# PowerSupply.net
KiCad netlist of a schematic drawn in Altium Designer
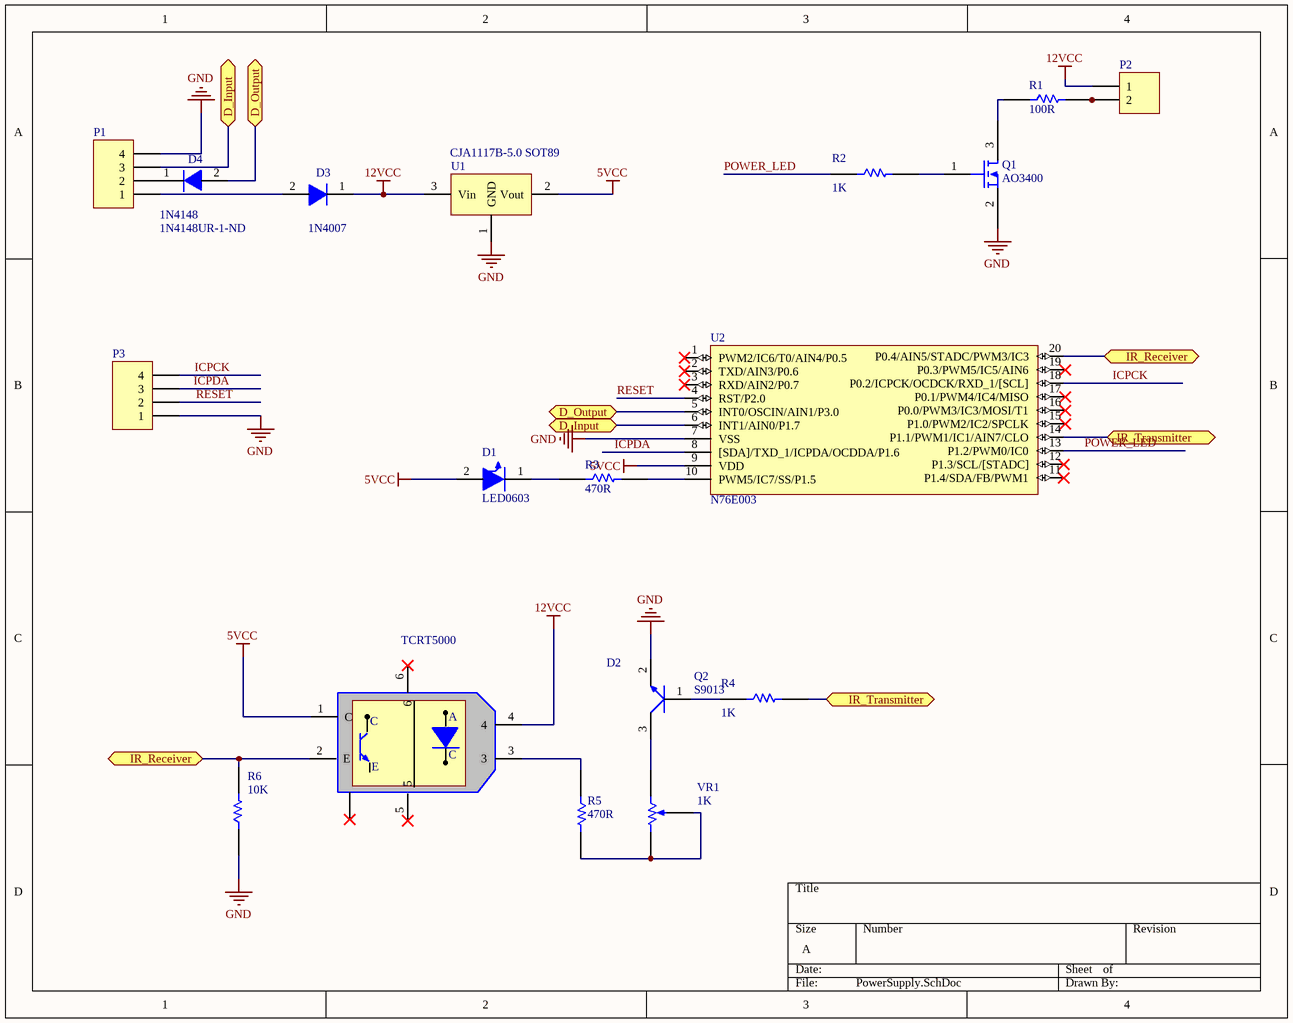
[diagram p0: PowerSupply.SchDoc]

(export (version "E")
  (design (tool "Eeschema 10.0.6"))
  (components
    (comp (ref "D1")
      (value "LED0603")
      (footprint "DIOC1608X06N")
      (libsource (lib "Integrated_Library1") (part "LED0603"))
    )
    (comp (ref "D2")
      (value "TCRT5000")
      (footprint "TCRT5000")
      (libsource (lib "Integrated_Library1") (part "TCRT5000"))
    )
    (comp (ref "D3")
      (value "1N4007")
      (footprint "SODFL504X244-2N")
      (description "1N4007_SMD")
      (libsource (lib "Integrated_Library1") (part "1N4007_SMD Diode"))
    )
    (comp (ref "D4")
      (value "1N4148")
      (footprint "DIOMELF3515N")
      (description "DIODE GEN PURP 75V 200MA DO213AA")
      (fields (field (name "SUPPLIER PART NUMBER 1") "1N4148UR-1-ND"))
      (libsource (lib "Integrated_Library1") (part "1N4148_SMD"))
    )
    (comp (ref "P1")
      (value "~")
      (footprint "HDR1X4H")
      (description "Header, 4-Pin, Right Angle")
      (fields (field (name "PUBLISHER") "Altium Limited"))
      (libsource (lib "Miscellaneous Connectors") (part "Header 4H"))
    )
    (comp (ref "P2")
      (value "~")
      (footprint "HDR1X2")
      (description "Header, 2-Pin")
      (fields (field (name "PUBLISHER") "Altium Limited"))
      (libsource (lib "Miscellaneous Connectors") (part "Header 2"))
    )
    (comp (ref "P3")
      (value "~")
      (footprint "HDR1X4")
      (description "Header, 4-Pin")
      (fields (field (name "PUBLISHER") "Altium Limited"))
      (libsource (lib "Miscellaneous Connectors") (part "Header 4"))
    )
    (comp (ref "Q1")
      (value "AO3400")
      (footprint "SOT95P278X125-3N")
      (description "AO3400  MOSFET SOT23-3")
      (libsource (lib "Integrated_Library1") (part "AO3400  MOSFET SOT23-3"))
    )
    (comp (ref "Q2")
      (value "S9013")
      (footprint "SOT95P278X125-3N")
      (description "SOT-23 Plastic-Encapsulate Transistors")
      (libsource (lib "Integrated_Library1") (part "Transitor S9013 NPN"))
    )
    (comp (ref "R1")
      (value "100R")
      (footprint "RESC2608X06N_0603")
      (description "Thick Film Resistors - SMD 0603 100OHMS 5% 1/10WATT")
      (libsource (lib "Integrated_Library1") (part "R100_0603_5%"))
    )
    (comp (ref "R2")
      (value "1K")
      (footprint "RESC2608X06N_0603")
      (description "Thick Film Resistors - SMD 0603 1kOHMS 5% 1/10WATT")
      (libsource (lib "Integrated_Library1") (part "1k_0603_5%"))
    )
    (comp (ref "R3")
      (value "470R")
      (footprint "RESC2608X06N_0603")
      (description "Thick Film Resistors - SMD 470 ohm 5%")
      (libsource (lib "Integrated_Library1") (part "R470_0603_5%"))
    )
    (comp (ref "R4")
      (value "1K")
      (footprint "RESC2608X06N_0603")
      (description "Thick Film Resistors - SMD 0603 1kOHMS 5% 1/10WATT")
      (libsource (lib "Integrated_Library1") (part "1k_0603_5%"))
    )
    (comp (ref "R5")
      (value "470R")
      (footprint "RESC2608X06N_0603")
      (description "Thick Film Resistors - SMD 470 ohm 5%")
      (libsource (lib "Integrated_Library1") (part "R470_0603_5%"))
    )
    (comp (ref "R6")
      (value "10K")
      (footprint "RESC2608X06N_0603")
      (description "RES SMD 10K OHM 1% 1/4W 0603")
      (libsource (lib "Integrated_Library1") (part "R10k_0603_5%"))
    )
    (comp (ref "U1")
      (value "CJA1117B-5.0 SOT89")
      (footprint "SOT89-150P409X160-3N")
      (description "CJA1117B-5.0 SOT89 Power IC 1A 5V_IC")
      (libsource (lib "Integrated_Library1") (part "CJA1117B-5.0 SOT89"))
    )
    (comp (ref "U2")
      (value "N76E003")
      (footprint "TSOP65P640X120-20N")
      (description "IC MCU 8BIT 18KB FLASH 20TSSOP")
      (libsource (lib "Integrated_Library1") (part "N76E003"))
    )
    (comp (ref "VR1")
      (value "1K")
      (footprint "Var_SMD_3x3")
      (description "Varistor 3x3 SMD 1KOhm 5% 1/10WATT")
      (libsource (lib "Integrated_Library1") (part "Varistor 3x3 SMD 1KOhm"))
    )
  )
  (nets
    (net (code "1") (name "/D_Input") (class "Default")
      (node (ref "P1") (pin "3") (pinfunction "3_3") (pintype "passive"))
      (node (ref "U2") (pin "6") (pinfunction "INT1/AIN0/P1.7_6") (pintype "bidirectional"))
    )
    (net (code "2") (name "/D_Output") (class "Default")
      (node (ref "D4") (pin "2") (pinfunction "A_2") (pintype "passive"))
      (node (ref "U2") (pin "5") (pinfunction "INT0/OSCIN/AIN1/P3.0_5") (pintype "bidirectional"))
    )
    (net (code "3") (name "/ICPCK") (class "Default")
      (node (ref "P3") (pin "4") (pinfunction "4_4") (pintype "passive"))
      (node (ref "U2") (pin "18") (pinfunction "P0.2/ICPCK/OCDCK/RXD_1/[SCL]_18") (pintype "bidirectional"))
    )
    (net (code "4") (name "/ICPDA") (class "Default")
      (node (ref "P3") (pin "3") (pinfunction "3_3") (pintype "passive"))
      (node (ref "U2") (pin "8") (pinfunction "[SDA]/TXD_1/ICPDA/OCDDA/P1.6_8") (pintype "power_in"))
    )
    (net (code "5") (name "/IR_Receiver") (class "Default")
      (node (ref "D2") (pin "2") (pinfunction "E_2") (pintype "passive"))
      (node (ref "R6") (pin "2") (pinfunction "2_2") (pintype "passive"))
      (node (ref "U2") (pin "20") (pinfunction "P0.4/AIN5/STADC/PWM3/IC3_20") (pintype "bidirectional"))
    )
    (net (code "6") (name "/IR_Transmitter") (class "Default")
      (node (ref "R4") (pin "2") (pinfunction "2_2") (pintype "passive"))
      (node (ref "U2") (pin "14") (pinfunction "P1.1/PWM1/IC1/AIN7/CLO_14") (pintype "bidirectional"))
    )
    (net (code "7") (name "/POWER_LED") (class "Default")
      (node (ref "R2") (pin "1") (pinfunction "1_1") (pintype "passive"))
      (node (ref "U2") (pin "13") (pinfunction "P1.2/PWM0/IC0_13") (pintype "bidirectional"))
    )
    (net (code "8") (name "/RESET") (class "Default")
      (node (ref "P3") (pin "2") (pinfunction "2_2") (pintype "passive"))
      (node (ref "U2") (pin "4") (pinfunction "RST/P2.0_4") (pintype "bidirectional"))
    )
    (net (code "9") (name "5VCC") (class "Default")
      (node (ref "D1") (pin "2") (pinfunction "C_2") (pintype "passive"))
      (node (ref "D2") (pin "1") (pinfunction "C_1") (pintype "passive"))
      (node (ref "U1") (pin "2") (pinfunction "Vout_2") (pintype "power_in"))
      (node (ref "U2") (pin "9") (pinfunction "VDD_9") (pintype "power_in"))
    )
    (net (code "10") (name "12VCC") (class "Default")
      (node (ref "D2") (pin "4") (pinfunction "4_4") (pintype "passive"))
      (node (ref "D3") (pin "1") (pinfunction "C_1") (pintype "passive"))
      (node (ref "P2") (pin "1") (pinfunction "1_1") (pintype "passive"))
      (node (ref "U1") (pin "3") (pinfunction "Vin_3") (pintype "power_in"))
    )
    (net (code "11") (name "GND") (class "Default")
      (node (ref "P1") (pin "4") (pinfunction "4_4") (pintype "passive"))
      (node (ref "P3") (pin "1") (pinfunction "1_1") (pintype "passive"))
      (node (ref "Q1") (pin "2") (pinfunction "S_2") (pintype "passive"))
      (node (ref "Q2") (pin "2") (pinfunction "C_2") (pintype "passive"))
      (node (ref "R6") (pin "1") (pinfunction "1_1") (pintype "passive"))
      (node (ref "U1") (pin "1") (pinfunction "GND_1") (pintype "power_in"))
      (node (ref "U2") (pin "7") (pinfunction "VSS_7") (pintype "power_in"))
    )
    (net (code "12") (name "Net-(D1-A)") (class "Default")
      (node (ref "D1") (pin "1") (pinfunction "A_1") (pintype "passive"))
      (node (ref "R3") (pin "1") (pinfunction "1_1") (pintype "passive"))
    )
    (net (code "13") (name "Net-(D2-Pad3)") (class "Default")
      (node (ref "D2") (pin "3") (pinfunction "3_3") (pintype "passive"))
      (node (ref "R5") (pin "1") (pinfunction "1_1") (pintype "passive"))
    )
    (net (code "14") (name "Net-(D3-A)") (class "Default")
      (node (ref "D3") (pin "2") (pinfunction "A_2") (pintype "passive"))
      (node (ref "P1") (pin "1") (pinfunction "1_1") (pintype "passive"))
    )
    (net (code "15") (name "Net-(P2-Pad2)") (class "Default")
      (node (ref "P2") (pin "2") (pinfunction "2_2") (pintype "passive"))
      (node (ref "R1") (pin "2") (pinfunction "2_2") (pintype "passive"))
    )
    (net (code "16") (name "Net-(Q1-D)") (class "Default")
      (node (ref "Q1") (pin "3") (pinfunction "D_3") (pintype "passive"))
      (node (ref "R1") (pin "1") (pinfunction "1_1") (pintype "passive"))
    )
    (net (code "17") (name "Net-(Q1-G)") (class "Default")
      (node (ref "Q1") (pin "1") (pinfunction "G_1") (pintype "passive"))
      (node (ref "R2") (pin "2") (pinfunction "2_2") (pintype "passive"))
    )
    (net (code "18") (name "Net-(Q2-B)") (class "Default")
      (node (ref "Q2") (pin "1") (pinfunction "B_1") (pintype "passive"))
      (node (ref "R4") (pin "1") (pinfunction "1_1") (pintype "passive"))
    )
    (net (code "19") (name "Net-(Q2-Pad3)") (class "Default")
      (node (ref "Q2") (pin "3") (pinfunction "3_3") (pintype "passive"))
      (node (ref "VR1") (pin "1") (pinfunction "1_1") (pintype "passive"))
    )
    (net (code "20") (name "Net-(R5-Pad2)") (class "Default")
      (node (ref "R5") (pin "2") (pinfunction "2_2") (pintype "passive"))
      (node (ref "VR1") (pin "2") (pinfunction "2_2") (pintype "passive"))
      (node (ref "VR1") (pin "3") (pinfunction "3_3") (pintype "passive"))
    )
    (net (code "21") (name "Net-(U2-PWM5{slash}IC7{slash}SS{slash}P1.5)") (class "Default")
      (node (ref "R3") (pin "2") (pinfunction "2_2") (pintype "passive"))
      (node (ref "U2") (pin "10") (pinfunction "PWM5/IC7/SS/P1.5_10") (pintype "power_in"))
    )
    (net (code "22") (name "unconnected-(D2-Pad5)") (class "Default")
      (node (ref "D2") (pin "5") (pinfunction "5_5") (pintype "passive+no_connect"))
    )
    (net (code "23") (name "unconnected-(D2-Pad6)") (class "Default")
      (node (ref "D2") (pin "6") (pinfunction "6_6") (pintype "passive+no_connect"))
    )
    (net (code "24") (name "unconnected-(D2-Pad7)") (class "Default")
      (node (ref "D2") (pin "7") (pinfunction "7_7") (pintype "passive+no_connect"))
    )
    (net (code "25") (name "unconnected-(D4-C-Pad1)") (class "Default")
      (node (ref "D4") (pin "1") (pinfunction "C_1") (pintype "passive"))
    )
    (net (code "26") (name "unconnected-(P1-Pad2)") (class "Default")
      (node (ref "P1") (pin "2") (pinfunction "2_2") (pintype "passive"))
    )
    (net (code "27") (name "unconnected-(U2-P0.0{slash}PWM3{slash}IC3{slash}MOSI{slash}T1-Pad16)") (class "Default")
      (node (ref "U2") (pin "16") (pinfunction "P0.0/PWM3/IC3/MOSI/T1_16") (pintype "bidirectional"))
    )
    (net (code "28") (name "unconnected-(U2-P0.1{slash}PWM4{slash}IC4{slash}MISO-Pad17)") (class "Default")
      (node (ref "U2") (pin "17") (pinfunction "P0.1/PWM4/IC4/MISO_17") (pintype "bidirectional"))
    )
    (net (code "29") (name "unconnected-(U2-P0.3{slash}PWM5{slash}IC5{slash}AIN6-Pad19)") (class "Default")
      (node (ref "U2") (pin "19") (pinfunction "P0.3/PWM5/IC5/AIN6_19") (pintype "bidirectional"))
    )
    (net (code "30") (name "unconnected-(U2-P1.0{slash}PWM2{slash}IC2{slash}SPCLK-Pad15)") (class "Default")
      (node (ref "U2") (pin "15") (pinfunction "P1.0/PWM2/IC2/SPCLK_15") (pintype "bidirectional"))
    )
    (net (code "31") (name "unconnected-(U2-P1.3{slash}SCL{slash}[STADC]-Pad12)") (class "Default")
      (node (ref "U2") (pin "12") (pinfunction "P1.3/SCL/[STADC]_12") (pintype "bidirectional+no_connect"))
    )
    (net (code "32") (name "unconnected-(U2-P1.4{slash}SDA{slash}FB{slash}PWM1-Pad11)") (class "Default")
      (node (ref "U2") (pin "11") (pinfunction "P1.4/SDA/FB/PWM1_11") (pintype "bidirectional+no_connect"))
    )
    (net (code "33") (name "unconnected-(U2-PWM2{slash}IC6{slash}T0{slash}AIN4{slash}P0.5-Pad1)") (class "Default")
      (node (ref "U2") (pin "1") (pinfunction "PWM2/IC6/T0/AIN4/P0.5_1") (pintype "bidirectional+no_connect"))
    )
    (net (code "34") (name "unconnected-(U2-RXD{slash}AIN2{slash}P0.7-Pad3)") (class "Default")
      (node (ref "U2") (pin "3") (pinfunction "RXD/AIN2/P0.7_3") (pintype "bidirectional+no_connect"))
    )
    (net (code "35") (name "unconnected-(U2-TXD{slash}AIN3{slash}P0.6-Pad2)") (class "Default")
      (node (ref "U2") (pin "2") (pinfunction "TXD/AIN3/P0.6_2") (pintype "bidirectional+no_connect"))
    )
  )
)
